# microSD.net
KiCad netlist of a schematic drawn in Altium Designer
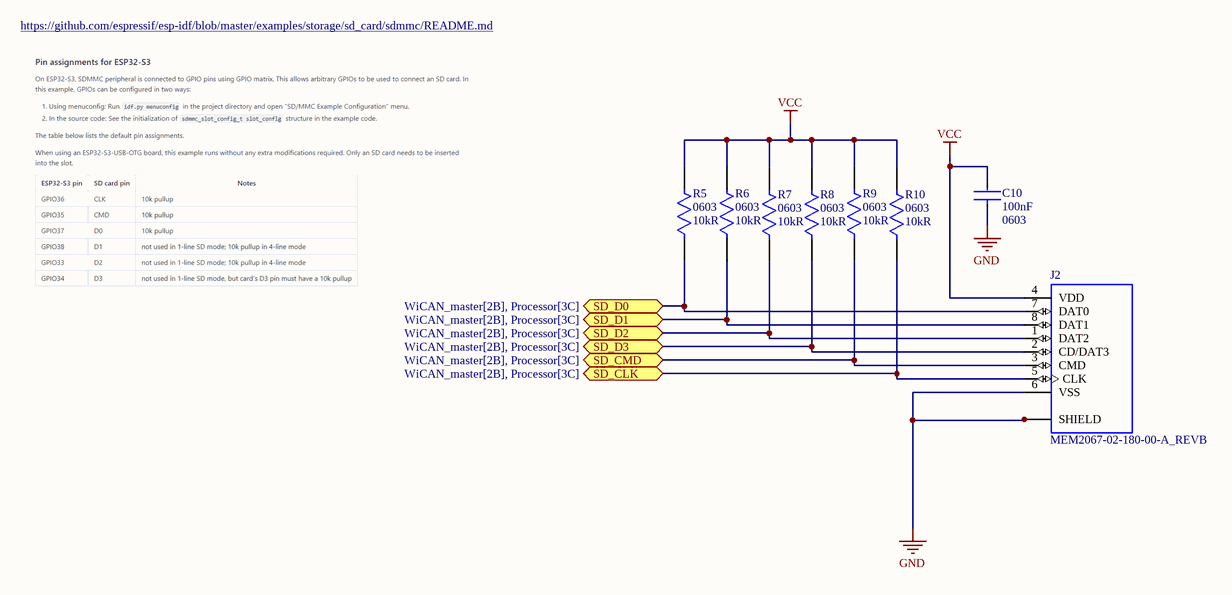
[diagram p0: microSD.SchDoc]

(export (version "E")
  (design (tool "Eeschema 10.0.6"))
  (components
    (comp (ref "C10")
      (value "CL10B104KB8WPNC")
      (footprint "FP-CL10-IPC_A")
      (description "Cap Ceramic 100nF 50V X7R ±10% Pad SMD 0603 +125°C T/R")
      (fields
        (field (name "CAPACITANCE") "100nF")
        (field (name "CASE/PACKAGE") "0603")
        (field (name "TOLERANCE") "10%")
      )
      (libsource (lib "Altium Content Vault") (part "b4654b650e69147ec39a6b967a45e02"))
    )
    (comp (ref "J2")
      (value "MEM2067-02-180-00-A_REVB")
      (footprint "GCT_MEM2067-02-180-00-A_REVB")
      (description "Micro SD Memory Card ConnectorSMT, Hinged, 1.80mm Profile")
      (libsource (lib "WiCAN_lib") (part "MEM2067-02-180-00-A_REVB"))
    )
    (comp (ref "R5")
      (value "RMCF0603JG10K0")
      (footprint "FP-RMCF0603-MFG")
      (description "10kΩ ±5% 0.1W 0603 Thick Film Chip Resistor AEC-Q200 compliant")
      (fields
        (field (name "TOLERANCE") "5%")
        (field (name "CASE CODE (IMPERIAL)") "0603")
        (field (name "RESISTANCE") "10kR")
      )
      (libsource (lib "Altium Content Vault") (part "1029c3af85768c4190bb7ad29bc67b5"))
    )
    (comp (ref "R6")
      (value "RMCF0603JG10K0")
      (footprint "FP-RMCF0603-MFG")
      (description "10kΩ ±5% 0.1W 0603 Thick Film Chip Resistor AEC-Q200 compliant")
      (fields
        (field (name "TOLERANCE") "5%")
        (field (name "CASE CODE (IMPERIAL)") "0603")
        (field (name "RESISTANCE") "10kR")
      )
      (libsource (lib "Altium Content Vault") (part "1029c3af85768c4190bb7ad29bc67b5"))
    )
    (comp (ref "R7")
      (value "RMCF0603JG10K0")
      (footprint "FP-RMCF0603-MFG")
      (description "10kΩ ±5% 0.1W 0603 Thick Film Chip Resistor AEC-Q200 compliant")
      (fields
        (field (name "TOLERANCE") "5%")
        (field (name "CASE CODE (IMPERIAL)") "0603")
        (field (name "RESISTANCE") "10kR")
      )
      (libsource (lib "Altium Content Vault") (part "1029c3af85768c4190bb7ad29bc67b5"))
    )
    (comp (ref "R8")
      (value "RMCF0603JG10K0")
      (footprint "FP-RMCF0603-MFG")
      (description "10kΩ ±5% 0.1W 0603 Thick Film Chip Resistor AEC-Q200 compliant")
      (fields
        (field (name "TOLERANCE") "5%")
        (field (name "CASE CODE (IMPERIAL)") "0603")
        (field (name "RESISTANCE") "10kR")
      )
      (libsource (lib "Altium Content Vault") (part "1029c3af85768c4190bb7ad29bc67b5"))
    )
    (comp (ref "R9")
      (value "RMCF0603JG10K0")
      (footprint "FP-RMCF0603-MFG")
      (description "10kΩ ±5% 0.1W 0603 Thick Film Chip Resistor AEC-Q200 compliant")
      (fields
        (field (name "TOLERANCE") "5%")
        (field (name "CASE CODE (IMPERIAL)") "0603")
        (field (name "RESISTANCE") "10kR")
      )
      (libsource (lib "Altium Content Vault") (part "1029c3af85768c4190bb7ad29bc67b5"))
    )
    (comp (ref "R10")
      (value "RMCF0603JG10K0")
      (footprint "FP-RMCF0603-MFG")
      (description "10kΩ ±5% 0.1W 0603 Thick Film Chip Resistor AEC-Q200 compliant")
      (fields
        (field (name "TOLERANCE") "5%")
        (field (name "CASE CODE (IMPERIAL)") "0603")
        (field (name "RESISTANCE") "10kR")
      )
      (libsource (lib "Altium Content Vault") (part "1029c3af85768c4190bb7ad29bc67b5"))
    )
  )
  (nets
    (net (code "1") (name "/SD_CLK") (class "Default")
      (node (ref "J2") (pin "5") (pinfunction "CLK_5") (pintype "bidirectional"))
      (node (ref "R10") (pin "1") (pinfunction "1_1") (pintype "passive"))
    )
    (net (code "2") (name "/SD_CMD") (class "Default")
      (node (ref "J2") (pin "3") (pinfunction "CMD_3") (pintype "bidirectional"))
      (node (ref "R9") (pin "1") (pinfunction "1_1") (pintype "passive"))
    )
    (net (code "3") (name "/SD_D0") (class "Default")
      (node (ref "J2") (pin "7") (pinfunction "DAT0_7") (pintype "bidirectional"))
      (node (ref "R5") (pin "1") (pinfunction "1_1") (pintype "passive"))
    )
    (net (code "4") (name "/SD_D1") (class "Default")
      (node (ref "J2") (pin "8") (pinfunction "DAT1_8") (pintype "bidirectional"))
      (node (ref "R6") (pin "1") (pinfunction "1_1") (pintype "passive"))
    )
    (net (code "5") (name "/SD_D2") (class "Default")
      (node (ref "J2") (pin "1") (pinfunction "DAT2_1") (pintype "bidirectional"))
      (node (ref "R7") (pin "1") (pinfunction "1_1") (pintype "passive"))
    )
    (net (code "6") (name "/SD_D3") (class "Default")
      (node (ref "J2") (pin "2") (pinfunction "CD/DAT3_2") (pintype "bidirectional"))
      (node (ref "R8") (pin "1") (pinfunction "1_1") (pintype "passive"))
    )
    (net (code "7") (name "GND") (class "Default")
      (node (ref "C10") (pin "1") (pinfunction "1_1") (pintype "passive"))
      (node (ref "J2") (pin "10") (pinfunction "SHIELD_10") (pintype "passive"))
      (node (ref "J2") (pin "11") (pinfunction "SHIELD_11") (pintype "passive"))
      (node (ref "J2") (pin "12") (pinfunction "SHIELD_12") (pintype "passive"))
      (node (ref "J2") (pin "6") (pinfunction "VSS_6") (pintype "power_in"))
      (node (ref "J2") (pin "9") (pinfunction "SHIELD_9") (pintype "passive"))
    )
    (net (code "8") (name "VCC") (class "Default")
      (node (ref "C10") (pin "2") (pinfunction "2_2") (pintype "passive"))
      (node (ref "J2") (pin "4") (pinfunction "VDD_4") (pintype "power_in"))
      (node (ref "R10") (pin "2") (pinfunction "2_2") (pintype "passive"))
      (node (ref "R5") (pin "2") (pinfunction "2_2") (pintype "passive"))
      (node (ref "R6") (pin "2") (pinfunction "2_2") (pintype "passive"))
      (node (ref "R7") (pin "2") (pinfunction "2_2") (pintype "passive"))
      (node (ref "R8") (pin "2") (pinfunction "2_2") (pintype "passive"))
      (node (ref "R9") (pin "2") (pinfunction "2_2") (pintype "passive"))
    )
  )
)
